# Adafruit_Feather_M0_Express.net
KiCad netlist of a schematic drawn in EAGLE
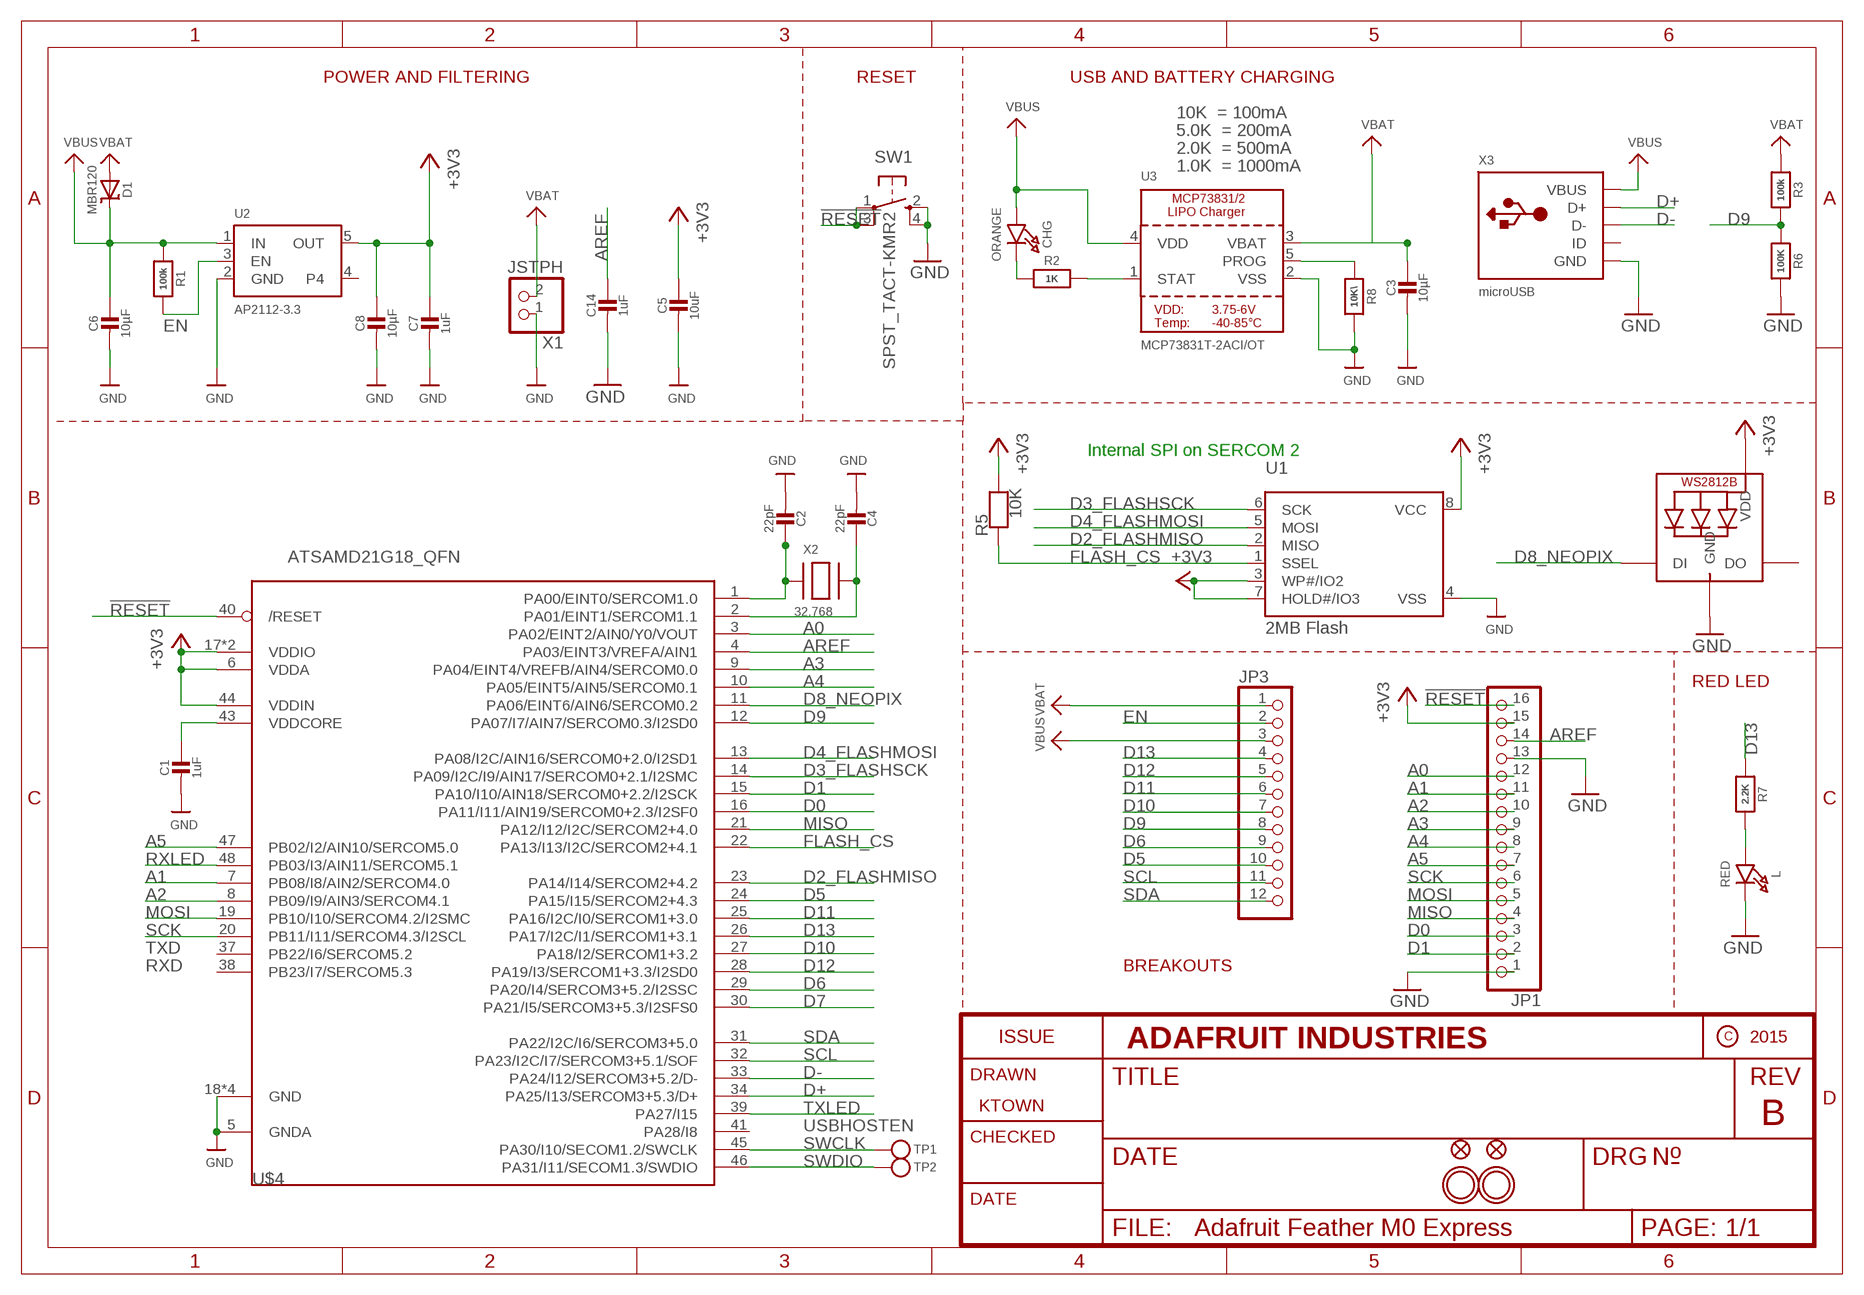
[diagram p0: schematic, sheet 1]

(export (version "E")
  (design (tool "Eeschema 10.0.6"))
  (components
    (comp (ref "C1")
      (value "1uF")
      (footprint "eagle-import:0603-NO")
      (libsource (lib "eagle-import") (part "CAP_CERAMIC0603_NO"))
    )
    (comp (ref "C2")
      (value "22pF")
      (footprint "eagle-import:0603-NO")
      (libsource (lib "eagle-import") (part "CAP_CERAMIC0603_NO"))
    )
    (comp (ref "C3")
      (value "10µF")
      (footprint "eagle-import:0805-NO")
      (libsource (lib "eagle-import") (part "CAP_CERAMIC0805-NOOUTLINE"))
    )
    (comp (ref "C4")
      (value "22pF")
      (footprint "eagle-import:0603-NO")
      (libsource (lib "eagle-import") (part "CAP_CERAMIC0603_NO"))
    )
    (comp (ref "C5")
      (value "10uF")
      (footprint "eagle-import:0805-NO")
      (libsource (lib "eagle-import") (part "CAP_CERAMIC0805-NOOUTLINE"))
    )
    (comp (ref "C6")
      (value "10µF")
      (footprint "eagle-import:0805-NO")
      (libsource (lib "eagle-import") (part "CAP_CERAMIC0805-NOOUTLINE"))
    )
    (comp (ref "C7")
      (value "1uF")
      (footprint "eagle-import:0603-NO")
      (libsource (lib "eagle-import") (part "CAP_CERAMIC0603_NO"))
    )
    (comp (ref "C8")
      (value "10µF")
      (footprint "eagle-import:0805-NO")
      (libsource (lib "eagle-import") (part "CAP_CERAMIC0805-NOOUTLINE"))
    )
    (comp (ref "C14")
      (value "1uF")
      (footprint "eagle-import:0603-NO")
      (libsource (lib "eagle-import") (part "CAP_CERAMIC0603_NO"))
    )
    (comp (ref "CHG")
      (value "ORANGE")
      (footprint "eagle-import:CHIPLED_0805_NOOUTLINE")
      (libsource (lib "eagle-import") (part "LED0805_NOOUTLINE"))
    )
    (comp (ref "D1")
      (value "MBR120")
      (footprint "eagle-import:SOD-123")
      (libsource (lib "eagle-import") (part "DIODE-SCHOTTKYSOD-123"))
    )
    (comp (ref "JP1")
      (value "HEADER-1X16ROUND")
      (footprint "eagle-import:1X16_ROUND")
      (libsource (lib "eagle-import") (part "HEADER-1X16ROUND"))
    )
    (comp (ref "JP3")
      (value "HEADER-1X12")
      (footprint "eagle-import:1X12_ROUND")
      (libsource (lib "eagle-import") (part "HEADER-1X12"))
    )
    (comp (ref "L")
      (value "RED")
      (footprint "eagle-import:CHIPLED_0805_NOOUTLINE")
      (libsource (lib "eagle-import") (part "LED0805_NOOUTLINE"))
    )
    (comp (ref "LED1")
      (value "WS2812B3535")
      (footprint "eagle-import:LED3535")
      (libsource (lib "eagle-import") (part "WS2812B3535"))
    )
    (comp (ref "R1")
      (value "100k")
      (footprint "eagle-import:0603-NO")
      (libsource (lib "eagle-import") (part "RESISTOR_0603_NOOUT"))
    )
    (comp (ref "R2")
      (value "1K")
      (footprint "eagle-import:0603-NO")
      (libsource (lib "eagle-import") (part "RESISTOR_0603_NOOUT"))
    )
    (comp (ref "R3")
      (value "100k")
      (footprint "eagle-import:0603-NO")
      (libsource (lib "eagle-import") (part "RESISTOR_0603_NOOUT"))
    )
    (comp (ref "R5")
      (value "10K")
      (footprint "eagle-import:0603-NO")
      (libsource (lib "eagle-import") (part "RESISTOR_0603_NOOUT"))
    )
    (comp (ref "R6")
      (value "100K")
      (footprint "eagle-import:0603-NO")
      (libsource (lib "eagle-import") (part "RESISTOR_0603_NOOUT"))
    )
    (comp (ref "R7")
      (value "2.2K")
      (footprint "eagle-import:0603-NO")
      (libsource (lib "eagle-import") (part "RESISTOR_0603_NOOUT"))
    )
    (comp (ref "R8")
      (value "10K\\")
      (footprint "eagle-import:0603-NO")
      (libsource (lib "eagle-import") (part "RESISTOR_0603_NOOUT"))
    )
    (comp (ref "SW1")
      (value "SPST_TACT-KMR2")
      (footprint "eagle-import:KMR2")
      (libsource (lib "eagle-import") (part "SPST_TACT-KMR2"))
    )
    (comp (ref "TP1")
      (value "TESTPOINTROUND1.5MM")
      (footprint "eagle-import:TESTPOINT_ROUND_1.5MM")
      (libsource (lib "eagle-import") (part "TESTPOINTROUND1.5MM"))
    )
    (comp (ref "TP2")
      (value "TESTPOINTROUND1.5MM")
      (footprint "eagle-import:TESTPOINT_ROUND_1.5MM")
      (libsource (lib "eagle-import") (part "TESTPOINTROUND1.5MM"))
    )
    (comp (ref "U$4")
      (value "ATSAMD21G18_QFN")
      (footprint "eagle-import:TQFN48_7MM")
      (libsource (lib "eagle-import") (part "ATSAMD21G_QFN"))
    )
    (comp (ref "U$31")
      (value "MOUNTINGHOLE2.5")
      (footprint "eagle-import:MOUNTINGHOLE_2.5_PLATED")
      (libsource (lib "eagle-import") (part "MOUNTINGHOLE2.5"))
    )
    (comp (ref "U$32")
      (value "MOUNTINGHOLE2.5")
      (footprint "eagle-import:MOUNTINGHOLE_2.5_PLATED")
      (libsource (lib "eagle-import") (part "MOUNTINGHOLE2.5"))
    )
    (comp (ref "U$34")
      (value "FIDUCIAL\"\"")
      (footprint "eagle-import:FIDUCIAL_1MM")
      (libsource (lib "eagle-import") (part "FIDUCIAL{dblquote}{dblquote}"))
    )
    (comp (ref "U$35")
      (value "FIDUCIAL\"\"")
      (footprint "eagle-import:FIDUCIAL_1MM")
      (libsource (lib "eagle-import") (part "FIDUCIAL{dblquote}{dblquote}"))
    )
    (comp (ref "U1")
      (value "2MB Flash")
      (footprint "eagle-import:SOIC8_208MIL")
      (libsource (lib "eagle-import") (part "SPIFLASH_SOIC8208MIL"))
    )
    (comp (ref "U2")
      (value "AP2112-3.3")
      (footprint "eagle-import:SOT23-5")
      (libsource (lib "eagle-import") (part "VREG_SOT23-5"))
    )
    (comp (ref "U3")
      (value "MCP73831T-2ACI/OT")
      (footprint "eagle-import:SOT23-5")
      (libsource (lib "eagle-import") (part "MCP73831/2"))
    )
    (comp (ref "X1")
      (value "JSTPH")
      (footprint "eagle-import:JSTPH2")
      (libsource (lib "eagle-import") (part "CON_JST_PH_2PIN"))
    )
    (comp (ref "X2")
      (value "32.768")
      (footprint "eagle-import:XTAL3215")
      (libsource (lib "eagle-import") (part "XTAL-3.2X1.5"))
    )
    (comp (ref "X3")
      (value "microUSB")
      (footprint "eagle-import:4UCONN_20329_V2")
      (libsource (lib "eagle-import") (part "USB_MICRO_20329_V2"))
    )
  )
  (nets
    (net (code "1") (name "+3V3") (class "Default")
      (node (ref "C5") (pin "1") (pinfunction "1_1") (pintype "passive"))
      (node (ref "C7") (pin "1") (pinfunction "1_1") (pintype "passive"))
      (node (ref "C8") (pin "1") (pinfunction "1_1") (pintype "passive"))
      (node (ref "JP1") (pin "15") (pinfunction "15_15") (pintype "passive"))
      (node (ref "LED1") (pin "2") (pinfunction "VDD_2") (pintype "power_in"))
      (node (ref "R5") (pin "2") (pinfunction "2_2") (pintype "passive"))
      (node (ref "U$4") (pin "17") (pinfunction "VDDIO_17") (pintype "power_in"))
      (node (ref "U$4") (pin "36") (pinfunction "VDDIO_36") (pintype "power_in"))
      (node (ref "U$4") (pin "44") (pinfunction "VDDIN_44") (pintype "power_in"))
      (node (ref "U$4") (pin "6") (pinfunction "VDDA_6") (pintype "power_in"))
      (node (ref "U1") (pin "3") (pinfunction "WP#/IO2_3") (pintype "bidirectional"))
      (node (ref "U1") (pin "7") (pinfunction "HOLD#/IO3_7") (pintype "bidirectional"))
      (node (ref "U1") (pin "8") (pinfunction "VCC_8") (pintype "bidirectional"))
      (node (ref "U2") (pin "5") (pinfunction "OUT_5") (pintype "power_in"))
    )
    (net (code "2") (name "/A0") (class "Default")
      (node (ref "JP1") (pin "12") (pinfunction "12_12") (pintype "passive"))
      (node (ref "U$4") (pin "3") (pinfunction "PA02/EINT2/AIN0/Y0/VOUT_3") (pintype "bidirectional"))
    )
    (net (code "3") (name "/A1") (class "Default")
      (node (ref "JP1") (pin "11") (pinfunction "11_11") (pintype "passive"))
      (node (ref "U$4") (pin "7") (pinfunction "PB08/I8/AIN2/SERCOM4.0_7") (pintype "bidirectional"))
    )
    (net (code "4") (name "/A2") (class "Default")
      (node (ref "JP1") (pin "10") (pinfunction "10_10") (pintype "passive"))
      (node (ref "U$4") (pin "8") (pinfunction "PB09/I9/AIN3/SERCOM4.1_8") (pintype "bidirectional"))
    )
    (net (code "5") (name "/A3") (class "Default")
      (node (ref "JP1") (pin "9") (pinfunction "9_9") (pintype "passive"))
      (node (ref "U$4") (pin "9") (pinfunction "PA04/EINT4/VREFB/AIN4/SERCOM0.0_9") (pintype "bidirectional"))
    )
    (net (code "6") (name "/A4") (class "Default")
      (node (ref "JP1") (pin "8") (pinfunction "8_8") (pintype "passive"))
      (node (ref "U$4") (pin "10") (pinfunction "PA05/EINT5/AIN5/SERCOM0.1_10") (pintype "bidirectional"))
    )
    (net (code "7") (name "/A5") (class "Default")
      (node (ref "JP1") (pin "7") (pinfunction "7_7") (pintype "passive"))
      (node (ref "U$4") (pin "47") (pinfunction "PB02/I2/AIN10/SERCOM5.0_47") (pintype "bidirectional"))
    )
    (net (code "8") (name "/AREF") (class "Default")
      (node (ref "C14") (pin "1") (pinfunction "1_1") (pintype "passive"))
      (node (ref "JP1") (pin "14") (pinfunction "14_14") (pintype "passive"))
      (node (ref "U$4") (pin "4") (pinfunction "PA03/EINT3/VREFA/AIN1_4") (pintype "bidirectional"))
    )
    (net (code "9") (name "/D+") (class "Default")
      (node (ref "U$4") (pin "34") (pinfunction "PA25/I13/SERCOM3+5.3/D+_34") (pintype "bidirectional"))
      (node (ref "X3") (pin "D+") (pinfunction "D+_D+") (pintype "bidirectional"))
    )
    (net (code "10") (name "/D-") (class "Default")
      (node (ref "U$4") (pin "33") (pinfunction "PA24/I12/SERCOM3+5.2/D-_33") (pintype "bidirectional"))
      (node (ref "X3") (pin "D-") (pinfunction "D-_D-") (pintype "bidirectional"))
    )
    (net (code "11") (name "/D0") (class "Default")
      (node (ref "JP1") (pin "3") (pinfunction "3_3") (pintype "passive"))
      (node (ref "U$4") (pin "16") (pinfunction "PA11/I11/AIN19/SERCOM0+2.3/I2SF0_16") (pintype "bidirectional"))
    )
    (net (code "12") (name "/D1") (class "Default")
      (node (ref "JP1") (pin "2") (pinfunction "2_2") (pintype "passive"))
      (node (ref "U$4") (pin "15") (pinfunction "PA10/I10/AIN18/SERCOM0+2.2/I2SCK_15") (pintype "bidirectional"))
    )
    (net (code "13") (name "/D2_FLASHMISO") (class "Default")
      (node (ref "U$4") (pin "23") (pinfunction "PA14/I14/SERCOM2+4.2_23") (pintype "bidirectional"))
      (node (ref "U1") (pin "2") (pinfunction "MISO_2") (pintype "bidirectional"))
    )
    (net (code "14") (name "/D3_FLASHSCK") (class "Default")
      (node (ref "U$4") (pin "14") (pinfunction "PA09/I2C/I9/AIN17/SERCOM0+2.1/I2SMC_14") (pintype "bidirectional"))
      (node (ref "U1") (pin "6") (pinfunction "SCK_6") (pintype "bidirectional"))
    )
    (net (code "15") (name "/D4_FLASHMOSI") (class "Default")
      (node (ref "U$4") (pin "13") (pinfunction "PA08/I2C/AIN16/SERCOM0+2.0/I2SD1_13") (pintype "bidirectional"))
      (node (ref "U1") (pin "5") (pinfunction "MOSI_5") (pintype "bidirectional"))
    )
    (net (code "16") (name "/D5") (class "Default")
      (node (ref "JP3") (pin "10") (pinfunction "10_10") (pintype "passive"))
      (node (ref "U$4") (pin "24") (pinfunction "PA15/I15/SERCOM2+4.3_24") (pintype "bidirectional"))
    )
    (net (code "17") (name "/D6") (class "Default")
      (node (ref "JP3") (pin "9") (pinfunction "9_9") (pintype "passive"))
      (node (ref "U$4") (pin "29") (pinfunction "PA20/I4/SERCOM3+5.2/I2SSC_29") (pintype "bidirectional"))
    )
    (net (code "18") (name "/D7") (class "Default")
      (node (ref "U$4") (pin "30") (pinfunction "PA21/I5/SERCOM3+5.3/I2SFS0_30") (pintype "bidirectional"))
    )
    (net (code "19") (name "/D8_NEOPIX") (class "Default")
      (node (ref "LED1") (pin "1") (pinfunction "DI_1") (pintype "input"))
      (node (ref "U$4") (pin "11") (pinfunction "PA06/EINT6/AIN6/SERCOM0.2_11") (pintype "bidirectional"))
    )
    (net (code "20") (name "/D9") (class "Default")
      (node (ref "JP3") (pin "8") (pinfunction "8_8") (pintype "passive"))
      (node (ref "R3") (pin "2") (pinfunction "2_2") (pintype "passive"))
      (node (ref "R6") (pin "1") (pinfunction "1_1") (pintype "passive"))
      (node (ref "U$4") (pin "12") (pinfunction "PA07/I7/AIN7/SERCOM0.3/I2SD0_12") (pintype "bidirectional"))
    )
    (net (code "21") (name "/D10") (class "Default")
      (node (ref "JP3") (pin "7") (pinfunction "7_7") (pintype "passive"))
      (node (ref "U$4") (pin "27") (pinfunction "PA18/I2/SERCOM1+3.2_27") (pintype "bidirectional"))
    )
    (net (code "22") (name "/D11") (class "Default")
      (node (ref "JP3") (pin "6") (pinfunction "6_6") (pintype "passive"))
      (node (ref "U$4") (pin "25") (pinfunction "PA16/I2C/I0/SERCOM1+3.0_25") (pintype "bidirectional"))
    )
    (net (code "23") (name "/D12") (class "Default")
      (node (ref "JP3") (pin "5") (pinfunction "5_5") (pintype "passive"))
      (node (ref "U$4") (pin "28") (pinfunction "PA19/I3/SERCOM1+3.3/I2SD0_28") (pintype "bidirectional"))
    )
    (net (code "24") (name "/D13") (class "Default")
      (node (ref "JP3") (pin "4") (pinfunction "4_4") (pintype "passive"))
      (node (ref "R7") (pin "1") (pinfunction "1_1") (pintype "passive"))
      (node (ref "U$4") (pin "26") (pinfunction "PA17/I2C/I1/SERCOM1+3.1_26") (pintype "bidirectional"))
    )
    (net (code "25") (name "/EN") (class "Default")
      (node (ref "JP3") (pin "2") (pinfunction "2_2") (pintype "passive"))
      (node (ref "R1") (pin "2") (pinfunction "2_2") (pintype "passive"))
      (node (ref "U2") (pin "3") (pinfunction "EN_3") (pintype "input"))
    )
    (net (code "26") (name "/FLASH_CS") (class "Default")
      (node (ref "R5") (pin "1") (pinfunction "1_1") (pintype "passive"))
      (node (ref "U$4") (pin "22") (pinfunction "PA13/I13/I2C/SERCOM2+4.1_22") (pintype "bidirectional"))
      (node (ref "U1") (pin "1") (pinfunction "SSEL_1") (pintype "bidirectional"))
    )
    (net (code "27") (name "/MISO") (class "Default")
      (node (ref "JP1") (pin "4") (pinfunction "4_4") (pintype "passive"))
      (node (ref "U$4") (pin "21") (pinfunction "PA12/I12/I2C/SERCOM2+4.0_21") (pintype "bidirectional"))
    )
    (net (code "28") (name "/MOSI") (class "Default")
      (node (ref "JP1") (pin "5") (pinfunction "5_5") (pintype "passive"))
      (node (ref "U$4") (pin "19") (pinfunction "PB10/I10/SERCOM4.2/I2SMC_19") (pintype "bidirectional"))
    )
    (net (code "29") (name "/RXLED") (class "Default")
      (node (ref "U$4") (pin "48") (pinfunction "PB03/I3/AIN11/SERCOM5.1_48") (pintype "bidirectional"))
    )
    (net (code "30") (name "/SCK") (class "Default")
      (node (ref "JP1") (pin "6") (pinfunction "6_6") (pintype "passive"))
      (node (ref "U$4") (pin "20") (pinfunction "PB11/I11/SERCOM4.3/I2SCL_20") (pintype "bidirectional"))
    )
    (net (code "31") (name "/SCL") (class "Default")
      (node (ref "JP3") (pin "11") (pinfunction "11_11") (pintype "passive"))
      (node (ref "U$4") (pin "32") (pinfunction "PA23/I2C/I7/SERCOM3+5.1/SOF_32") (pintype "bidirectional"))
    )
    (net (code "32") (name "/SDA") (class "Default")
      (node (ref "JP3") (pin "12") (pinfunction "12_12") (pintype "passive"))
      (node (ref "U$4") (pin "31") (pinfunction "PA22/I2C/I6/SERCOM3+5.0_31") (pintype "bidirectional"))
    )
    (net (code "33") (name "/SWCLK") (class "Default")
      (node (ref "TP1") (pin "P$1") (pinfunction "P$1_P$1") (pintype "bidirectional"))
      (node (ref "U$4") (pin "45") (pinfunction "PA30/I10/SECOM1.2/SWCLK_45") (pintype "bidirectional"))
    )
    (net (code "34") (name "/SWDIO") (class "Default")
      (node (ref "TP2") (pin "P$1") (pinfunction "P$1_P$1") (pintype "bidirectional"))
      (node (ref "U$4") (pin "46") (pinfunction "PA31/I11/SECOM1.3/SWDIO_46") (pintype "bidirectional"))
    )
    (net (code "35") (name "/TXLED") (class "Default")
      (node (ref "U$4") (pin "39") (pinfunction "PA27/I15_39") (pintype "bidirectional"))
    )
    (net (code "36") (name "/~{RESET}") (class "Default")
      (node (ref "JP1") (pin "16") (pinfunction "16_16") (pintype "passive"))
      (node (ref "SW1") (pin "1") (pinfunction "P_1") (pintype "passive"))
      (node (ref "SW1") (pin "3") (pinfunction "P1_3") (pintype "passive"))
      (node (ref "U$4") (pin "40") (pinfunction "/RESET_40") (pintype "bidirectional"))
    )
    (net (code "37") (name "GND") (class "Default")
      (node (ref "C1") (pin "2") (pinfunction "2_2") (pintype "passive"))
      (node (ref "C14") (pin "2") (pinfunction "2_2") (pintype "passive"))
      (node (ref "C2") (pin "2") (pinfunction "2_2") (pintype "passive"))
      (node (ref "C3") (pin "2") (pinfunction "2_2") (pintype "passive"))
      (node (ref "C4") (pin "2") (pinfunction "2_2") (pintype "passive"))
      (node (ref "C5") (pin "2") (pinfunction "2_2") (pintype "passive"))
      (node (ref "C6") (pin "2") (pinfunction "2_2") (pintype "passive"))
      (node (ref "C7") (pin "2") (pinfunction "2_2") (pintype "passive"))
      (node (ref "C8") (pin "2") (pinfunction "2_2") (pintype "passive"))
      (node (ref "JP1") (pin "1") (pinfunction "1_1") (pintype "passive"))
      (node (ref "JP1") (pin "13") (pinfunction "13_13") (pintype "passive"))
      (node (ref "L") (pin "C") (pinfunction "C_C") (pintype "passive"))
      (node (ref "LED1") (pin "4") (pinfunction "GND_4") (pintype "power_in"))
      (node (ref "R6") (pin "2") (pinfunction "2_2") (pintype "passive"))
      (node (ref "R8") (pin "2") (pinfunction "2_2") (pintype "passive"))
      (node (ref "SW1") (pin "2") (pinfunction "S_2") (pintype "passive"))
      (node (ref "SW1") (pin "4") (pinfunction "S1_4") (pintype "passive"))
      (node (ref "U$4") (pin "18") (pinfunction "GND_18") (pintype "power_in"))
      (node (ref "U$4") (pin "35") (pinfunction "GND_35") (pintype "power_in"))
      (node (ref "U$4") (pin "42") (pinfunction "GND_42") (pintype "power_in"))
      (node (ref "U$4") (pin "5") (pinfunction "GNDA_5") (pintype "power_in"))
      (node (ref "U$4") (pin "THERMAL") (pinfunction "GND_THERMAL") (pintype "power_in"))
      (node (ref "U1") (pin "4") (pinfunction "VSS_4") (pintype "bidirectional"))
      (node (ref "U2") (pin "2") (pinfunction "GND_2") (pintype "power_in"))
      (node (ref "U3") (pin "2") (pinfunction "VSS_2") (pintype "power_in"))
      (node (ref "X1") (pin "1") (pinfunction "1_1") (pintype "passive"))
      (node (ref "X3") (pin "BASE@1") (pinfunction "GND_BASE@1") (pintype "power_in"))
      (node (ref "X3") (pin "BASE@2") (pinfunction "GND_BASE@2") (pintype "power_in"))
      (node (ref "X3") (pin "GND") (pinfunction "GND_GND") (pintype "power_in"))
      (node (ref "X3") (pin "SPRT@1") (pinfunction "GND_SPRT@1") (pintype "power_in"))
      (node (ref "X3") (pin "SPRT@2") (pinfunction "GND_SPRT@2") (pintype "power_in"))
      (node (ref "X3") (pin "SPRT@3") (pinfunction "GND_SPRT@3") (pintype "power_in"))
      (node (ref "X3") (pin "SPRT@4") (pinfunction "GND_SPRT@4") (pintype "power_in"))
    )
    (net (code "38") (name "Net-(CHG-PadC)") (class "Default")
      (node (ref "CHG") (pin "C") (pinfunction "C_C") (pintype "passive"))
      (node (ref "R2") (pin "1") (pinfunction "1_1") (pintype "passive"))
    )
    (net (code "39") (name "Net-(L-PadA)") (class "Default")
      (node (ref "L") (pin "A") (pinfunction "A_A") (pintype "passive"))
      (node (ref "R7") (pin "2") (pinfunction "2_2") (pintype "passive"))
    )
    (net (code "40") (name "Net-(U$4-PA00{slash}EINT0{slash}SERCOM1.0)") (class "Default")
      (node (ref "C2") (pin "1") (pinfunction "1_1") (pintype "passive"))
      (node (ref "U$4") (pin "1") (pinfunction "PA00/EINT0/SERCOM1.0_1") (pintype "bidirectional"))
      (node (ref "X2") (pin "P$1") (pinfunction "P$1_P$1") (pintype "bidirectional"))
    )
    (net (code "41") (name "Net-(U$4-PA01{slash}EINT1{slash}SERCOM1.1)") (class "Default")
      (node (ref "C4") (pin "1") (pinfunction "1_1") (pintype "passive"))
      (node (ref "U$4") (pin "2") (pinfunction "PA01/EINT1/SERCOM1.1_2") (pintype "bidirectional"))
      (node (ref "X2") (pin "P$2") (pinfunction "P$2_P$2") (pintype "bidirectional"))
    )
    (net (code "42") (name "Net-(U$4-VDDCORE)") (class "Default")
      (node (ref "C1") (pin "1") (pinfunction "1_1") (pintype "passive"))
      (node (ref "U$4") (pin "43") (pinfunction "VDDCORE_43") (pintype "power_in"))
    )
    (net (code "43") (name "Net-(U3-PROG)") (class "Default")
      (node (ref "R8") (pin "1") (pinfunction "1_1") (pintype "passive"))
      (node (ref "U3") (pin "5") (pinfunction "PROG_5") (pintype "input"))
    )
    (net (code "44") (name "Net-(U3-STAT)") (class "Default")
      (node (ref "R2") (pin "2") (pinfunction "2_2") (pintype "passive"))
      (node (ref "U3") (pin "1") (pinfunction "STAT_1") (pintype "output"))
    )
    (net (code "45") (name "VBAT") (class "Default")
      (node (ref "C3") (pin "1") (pinfunction "1_1") (pintype "passive"))
      (node (ref "D1") (pin "A") (pinfunction "A_A") (pintype "passive"))
      (node (ref "JP3") (pin "1") (pinfunction "1_1") (pintype "passive"))
      (node (ref "R3") (pin "1") (pinfunction "1_1") (pintype "passive"))
      (node (ref "U3") (pin "3") (pinfunction "VBAT_3") (pintype "power_in"))
      (node (ref "X1") (pin "2") (pinfunction "2_2") (pintype "passive"))
    )
    (net (code "46") (name "VBUS") (class "Default")
      (node (ref "C6") (pin "1") (pinfunction "1_1") (pintype "passive"))
      (node (ref "CHG") (pin "A") (pinfunction "A_A") (pintype "passive"))
      (node (ref "D1") (pin "C") (pinfunction "C_C") (pintype "passive"))
      (node (ref "JP3") (pin "3") (pinfunction "3_3") (pintype "passive"))
      (node (ref "R1") (pin "1") (pinfunction "1_1") (pintype "passive"))
      (node (ref "U2") (pin "1") (pinfunction "IN_1") (pintype "power_in"))
      (node (ref "U3") (pin "4") (pinfunction "VDD_4") (pintype "power_in"))
      (node (ref "X3") (pin "VBUS") (pinfunction "VBUS_VBUS") (pintype "power_in"))
    )
    (net (code "47") (name "unconnected-(LED1-DO-Pad3)") (class "Default")
      (node (ref "LED1") (pin "3") (pinfunction "DO_3") (pintype "output"))
    )
    (net (code "48") (name "unconnected-(U$4-PA28{slash}I8-Pad41)") (class "Default")
      (node (ref "U$4") (pin "41") (pinfunction "PA28/I8_41") (pintype "bidirectional"))
    )
    (net (code "49") (name "unconnected-(U$4-PB22{slash}I6{slash}SERCOM5.2-Pad37)") (class "Default")
      (node (ref "U$4") (pin "37") (pinfunction "PB22/I6/SERCOM5.2_37") (pintype "bidirectional"))
    )
    (net (code "50") (name "unconnected-(U$4-PB23{slash}I7{slash}SERCOM5.3-Pad38)") (class "Default")
      (node (ref "U$4") (pin "38") (pinfunction "PB23/I7/SERCOM5.3_38") (pintype "bidirectional"))
    )
    (net (code "51") (name "unconnected-(U2-P4-Pad4)") (class "Default")
      (node (ref "U2") (pin "4") (pinfunction "P4_4") (pintype "bidirectional"))
    )
    (net (code "52") (name "unconnected-(X3-PadID)") (class "Default")
      (node (ref "X3") (pin "ID") (pinfunction "ID_ID") (pintype "bidirectional"))
    )
  )
)
